# Buttons.net
KiCad netlist of a schematic drawn in Altium Designer
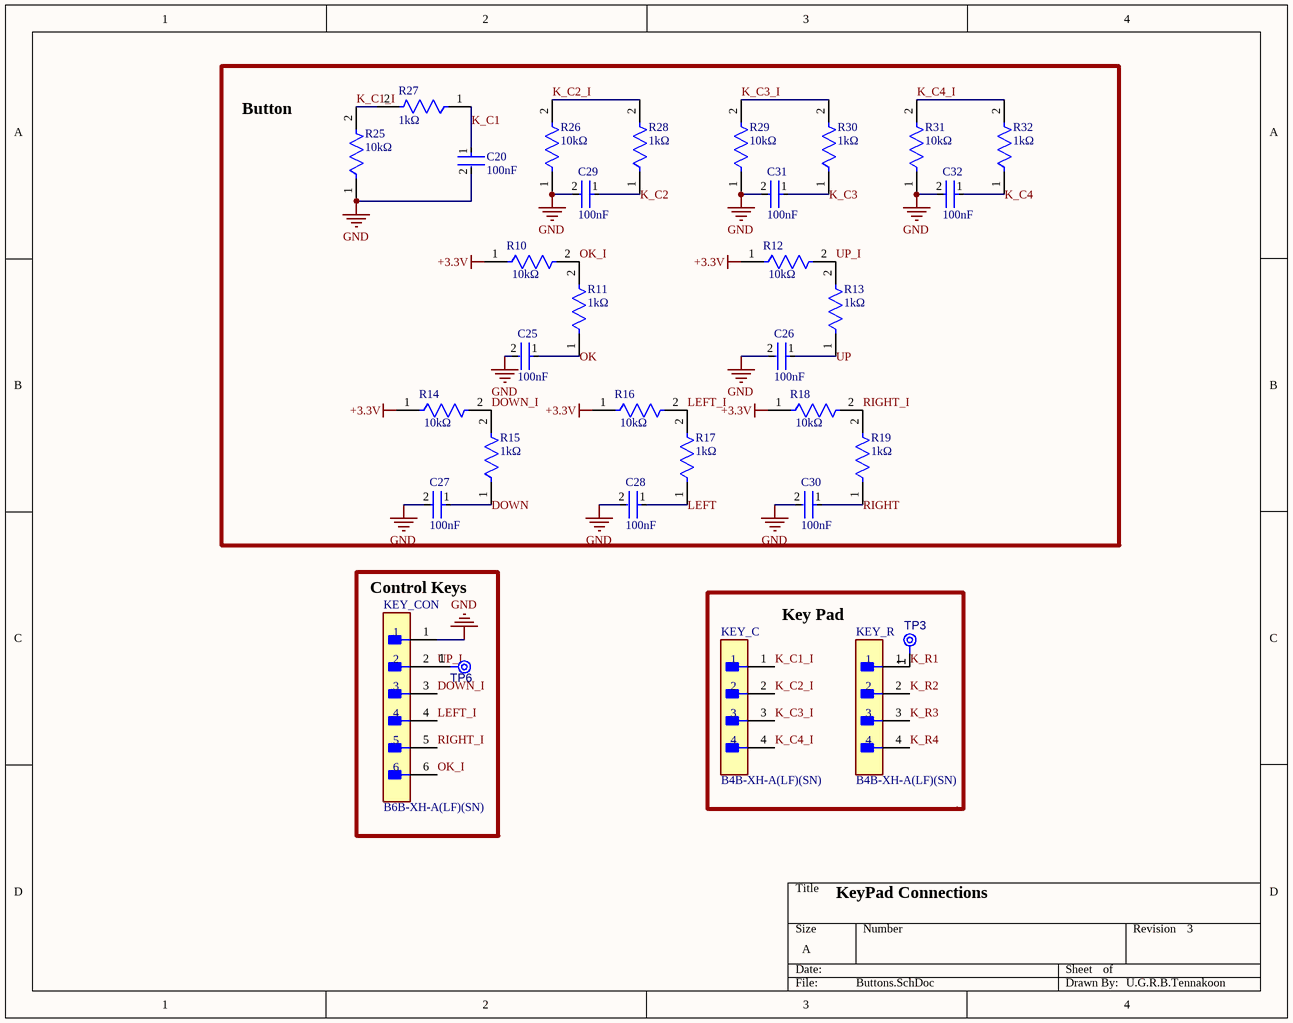
[diagram p0: Buttons.SchDoc]

(export (version "E")
  (design (tool "Eeschema 10.0.6"))
  (components
    (comp (ref "C20")
      (value "100nF")
      (footprint "FP-CL21-IPC_A")
      (description "CL21B104KCFWPNE CL21 Series 0805 100nF 100V ±10% Tolerance X7R Multilayer Ceramic Chip Capacitor")
      (fields (field (name "TOLERANCE") "10%"))
      (libsource (lib "Altium Content Vault") (part "b4654b650e69147ec39a6b967a45e02"))
    )
    (comp (ref "C25")
      (value "100nF")
      (footprint "FP-CL21-IPC_A")
      (description "CL21B104KCFWPNE CL21 Series 0805 100nF 100V ±10% Tolerance X7R Multilayer Ceramic Chip Capacitor")
      (fields (field (name "TOLERANCE") "10%"))
      (libsource (lib "Altium Content Vault") (part "b4654b650e69147ec39a6b967a45e02"))
    )
    (comp (ref "C26")
      (value "100nF")
      (footprint "FP-CL21-IPC_A")
      (description "CL21B104KCFWPNE CL21 Series 0805 100nF 100V ±10% Tolerance X7R Multilayer Ceramic Chip Capacitor")
      (fields (field (name "TOLERANCE") "10%"))
      (libsource (lib "Altium Content Vault") (part "b4654b650e69147ec39a6b967a45e02"))
    )
    (comp (ref "C27")
      (value "100nF")
      (footprint "FP-CL21-IPC_A")
      (description "CL21B104KCFWPNE CL21 Series 0805 100nF 100V ±10% Tolerance X7R Multilayer Ceramic Chip Capacitor")
      (fields (field (name "TOLERANCE") "10%"))
      (libsource (lib "Altium Content Vault") (part "b4654b650e69147ec39a6b967a45e02"))
    )
    (comp (ref "C28")
      (value "100nF")
      (footprint "FP-CL21-IPC_A")
      (description "CL21B104KCFWPNE CL21 Series 0805 100nF 100V ±10% Tolerance X7R Multilayer Ceramic Chip Capacitor")
      (fields (field (name "TOLERANCE") "10%"))
      (libsource (lib "Altium Content Vault") (part "b4654b650e69147ec39a6b967a45e02"))
    )
    (comp (ref "C29")
      (value "100nF")
      (footprint "FP-CL21-IPC_A")
      (description "CL21B104KCFWPNE CL21 Series 0805 100nF 100V ±10% Tolerance X7R Multilayer Ceramic Chip Capacitor")
      (fields (field (name "TOLERANCE") "10%"))
      (libsource (lib "Altium Content Vault") (part "b4654b650e69147ec39a6b967a45e02"))
    )
    (comp (ref "C30")
      (value "100nF")
      (footprint "FP-CL21-IPC_A")
      (description "CL21B104KCFWPNE CL21 Series 0805 100nF 100V ±10% Tolerance X7R Multilayer Ceramic Chip Capacitor")
      (fields (field (name "TOLERANCE") "10%"))
      (libsource (lib "Altium Content Vault") (part "b4654b650e69147ec39a6b967a45e02"))
    )
    (comp (ref "C31")
      (value "100nF")
      (footprint "FP-CL21-IPC_A")
      (description "CL21B104KCFWPNE CL21 Series 0805 100nF 100V ±10% Tolerance X7R Multilayer Ceramic Chip Capacitor")
      (fields (field (name "TOLERANCE") "10%"))
      (libsource (lib "Altium Content Vault") (part "b4654b650e69147ec39a6b967a45e02"))
    )
    (comp (ref "C32")
      (value "100nF")
      (footprint "FP-CL21-IPC_A")
      (description "CL21B104KCFWPNE CL21 Series 0805 100nF 100V ±10% Tolerance X7R Multilayer Ceramic Chip Capacitor")
      (fields (field (name "TOLERANCE") "10%"))
      (libsource (lib "Altium Content Vault") (part "b4654b650e69147ec39a6b967a45e02"))
    )
    (comp (ref "KEY_C")
      (value "B4B-XH-A(LF)(SN)")
      (footprint "FP-B4B-XH-A_LF_SN-MFG")
      (description "CONN HEADER VERT 4POS 2.5MM")
      (libsource (lib "Altium Content Vault") (part "299a8cea1bdcbc3624fe62c390fa72c"))
    )
    (comp (ref "KEY_CON")
      (value "B6B-XH-A(LF)(SN)")
      (footprint "FP-B6B-XH-A_LF_SN-MFG")
      (description "CONN HEADER VERT 6POS 2.5MM")
      (libsource (lib "Altium Content Vault") (part "f2cb566baf1c37ab5a3b8e90bbeafd6"))
    )
    (comp (ref "KEY_R")
      (value "B4B-XH-A(LF)(SN)")
      (footprint "FP-B4B-XH-A_LF_SN-MFG")
      (description "CONN HEADER VERT 4POS 2.5MM")
      (libsource (lib "Altium Content Vault") (part "299a8cea1bdcbc3624fe62c390fa72c"))
    )
    (comp (ref "R10")
      (value "10kΩ")
      (footprint "FP-SR0805-MFG")
      (description "RES SMD 0805 1/2W 1% 10K OHM")
      (fields (field (name "MANUFACTURER PART NUMBER") "SR0805FR-4710KL") (field (name "TOLERANCE") "0.01"))
      (libsource (lib "Altium Content Vault") (part "1029c3af85768c4190bb7ad29bc67b5"))
    )
    (comp (ref "R11")
      (value "1kΩ")
      (footprint "FP-SR0805-MFG")
      (description "RMC08051K5%N")
      (fields (field (name "MANUFACTURER PART NUMBER") "SR0805FR-4710KL") (field (name "TOLERANCE") "0.01"))
      (libsource (lib "Altium Content Vault") (part "1029c3af85768c4190bb7ad29bc67b5"))
    )
    (comp (ref "R12")
      (value "10kΩ")
      (footprint "FP-SR0805-MFG")
      (description "RES SMD 0805 1/2W 1% 10K OHM")
      (fields (field (name "MANUFACTURER PART NUMBER") "SR0805FR-4710KL") (field (name "TOLERANCE") "0.01"))
      (libsource (lib "Altium Content Vault") (part "1029c3af85768c4190bb7ad29bc67b5"))
    )
    (comp (ref "R13")
      (value "1kΩ")
      (footprint "FP-SR0805-MFG")
      (description "RMC08051K5%N")
      (fields (field (name "MANUFACTURER PART NUMBER") "SR0805FR-4710KL") (field (name "TOLERANCE") "0.01"))
      (libsource (lib "Altium Content Vault") (part "1029c3af85768c4190bb7ad29bc67b5"))
    )
    (comp (ref "R14")
      (value "10kΩ")
      (footprint "FP-SR0805-MFG")
      (description "RES SMD 0805 1/2W 1% 10K OHM")
      (fields (field (name "MANUFACTURER PART NUMBER") "SR0805FR-4710KL") (field (name "TOLERANCE") "0.01"))
      (libsource (lib "Altium Content Vault") (part "1029c3af85768c4190bb7ad29bc67b5"))
    )
    (comp (ref "R15")
      (value "1kΩ")
      (footprint "FP-SR0805-MFG")
      (description "RMC08051K5%N")
      (fields (field (name "MANUFACTURER PART NUMBER") "SR0805FR-4710KL") (field (name "TOLERANCE") "0.01"))
      (libsource (lib "Altium Content Vault") (part "1029c3af85768c4190bb7ad29bc67b5"))
    )
    (comp (ref "R16")
      (value "10kΩ")
      (footprint "FP-SR0805-MFG")
      (description "RES SMD 0805 1/2W 1% 10K OHM")
      (fields (field (name "MANUFACTURER PART NUMBER") "SR0805FR-4710KL") (field (name "TOLERANCE") "0.01"))
      (libsource (lib "Altium Content Vault") (part "1029c3af85768c4190bb7ad29bc67b5"))
    )
    (comp (ref "R17")
      (value "1kΩ")
      (footprint "FP-SR0805-MFG")
      (description "RMC08051K5%N")
      (fields (field (name "MANUFACTURER PART NUMBER") "SR0805FR-4710KL") (field (name "TOLERANCE") "0.01"))
      (libsource (lib "Altium Content Vault") (part "1029c3af85768c4190bb7ad29bc67b5"))
    )
    (comp (ref "R18")
      (value "10kΩ")
      (footprint "FP-SR0805-MFG")
      (description "RES SMD 0805 1/2W 1% 10K OHM")
      (fields (field (name "MANUFACTURER PART NUMBER") "SR0805FR-4710KL") (field (name "TOLERANCE") "0.01"))
      (libsource (lib "Altium Content Vault") (part "1029c3af85768c4190bb7ad29bc67b5"))
    )
    (comp (ref "R19")
      (value "1kΩ")
      (footprint "FP-SR0805-MFG")
      (description "RMC08051K5%N")
      (fields (field (name "MANUFACTURER PART NUMBER") "SR0805FR-4710KL") (field (name "TOLERANCE") "0.01"))
      (libsource (lib "Altium Content Vault") (part "1029c3af85768c4190bb7ad29bc67b5"))
    )
    (comp (ref "R25")
      (value "10kΩ")
      (footprint "FP-SR0805-MFG")
      (description "RES SMD 0805 1/2W 1% 10K OHM")
      (fields (field (name "MANUFACTURER PART NUMBER") "SR0805FR-4710KL") (field (name "TOLERANCE") "0.01"))
      (libsource (lib "Altium Content Vault") (part "1029c3af85768c4190bb7ad29bc67b5"))
    )
    (comp (ref "R26")
      (value "10kΩ")
      (footprint "FP-SR0805-MFG")
      (description "RES SMD 0805 1/2W 1% 10K OHM")
      (fields (field (name "MANUFACTURER PART NUMBER") "SR0805FR-4710KL") (field (name "TOLERANCE") "0.01"))
      (libsource (lib "Altium Content Vault") (part "1029c3af85768c4190bb7ad29bc67b5"))
    )
    (comp (ref "R27")
      (value "1kΩ")
      (footprint "FP-SR0805-MFG")
      (description "RMC08051K5%N")
      (fields (field (name "MANUFACTURER PART NUMBER") "SR0805FR-4710KL") (field (name "TOLERANCE") "0.01"))
      (libsource (lib "Altium Content Vault") (part "1029c3af85768c4190bb7ad29bc67b5"))
    )
    (comp (ref "R28")
      (value "1kΩ")
      (footprint "FP-SR0805-MFG")
      (description "RMC08051K5%N")
      (fields (field (name "MANUFACTURER PART NUMBER") "SR0805FR-4710KL") (field (name "TOLERANCE") "0.01"))
      (libsource (lib "Altium Content Vault") (part "1029c3af85768c4190bb7ad29bc67b5"))
    )
    (comp (ref "R29")
      (value "10kΩ")
      (footprint "FP-SR0805-MFG")
      (description "RES SMD 0805 1/2W 1% 10K OHM")
      (fields (field (name "MANUFACTURER PART NUMBER") "SR0805FR-4710KL") (field (name "TOLERANCE") "0.01"))
      (libsource (lib "Altium Content Vault") (part "1029c3af85768c4190bb7ad29bc67b5"))
    )
    (comp (ref "R30")
      (value "1kΩ")
      (footprint "FP-SR0805-MFG")
      (description "RMC08051K5%N")
      (fields (field (name "MANUFACTURER PART NUMBER") "SR0805FR-4710KL") (field (name "TOLERANCE") "0.01"))
      (libsource (lib "Altium Content Vault") (part "1029c3af85768c4190bb7ad29bc67b5"))
    )
    (comp (ref "R31")
      (value "10kΩ")
      (footprint "FP-SR0805-MFG")
      (description "RES SMD 0805 1/2W 1% 10K OHM")
      (fields (field (name "MANUFACTURER PART NUMBER") "SR0805FR-4710KL") (field (name "TOLERANCE") "0.01"))
      (libsource (lib "Altium Content Vault") (part "1029c3af85768c4190bb7ad29bc67b5"))
    )
    (comp (ref "R32")
      (value "1kΩ")
      (footprint "FP-SR0805-MFG")
      (description "RMC08051K5%N")
      (fields (field (name "MANUFACTURER PART NUMBER") "SR0805FR-4710KL") (field (name "TOLERANCE") "0.01"))
      (libsource (lib "Altium Content Vault") (part "1029c3af85768c4190bb7ad29bc67b5"))
    )
    (comp (ref "TP3")
      (value "TPAD6R")
      (footprint "TP06R")
      (description "0.6mm round")
      (libsource (lib "ravindu tennakoon") (part "CMP-001-0001-4"))
    )
    (comp (ref "TP6")
      (value "TPAD6R")
      (footprint "TP06R")
      (description "0.6mm round")
      (libsource (lib "ravindu tennakoon") (part "CMP-001-0001-4"))
    )
  )
  (nets
    (net (code "1") (name "+3.3V") (class "Default")
      (node (ref "R10") (pin "1") (pinfunction "1_1") (pintype "passive"))
      (node (ref "R12") (pin "1") (pinfunction "1_1") (pintype "passive"))
      (node (ref "R14") (pin "1") (pinfunction "1_1") (pintype "passive"))
      (node (ref "R16") (pin "1") (pinfunction "1_1") (pintype "passive"))
      (node (ref "R18") (pin "1") (pinfunction "1_1") (pintype "passive"))
    )
    (net (code "2") (name "/DOWN") (class "Default")
      (node (ref "C27") (pin "1") (pinfunction "1_1") (pintype "passive"))
      (node (ref "R15") (pin "1") (pinfunction "1_1") (pintype "passive"))
    )
    (net (code "3") (name "/DOWN_I") (class "Default")
      (node (ref "KEY_CON") (pin "3") (pinfunction "3_3") (pintype "passive"))
      (node (ref "R14") (pin "2") (pinfunction "2_2") (pintype "passive"))
      (node (ref "R15") (pin "2") (pinfunction "2_2") (pintype "passive"))
    )
    (net (code "4") (name "/K_C1") (class "Default")
      (node (ref "C20") (pin "1") (pinfunction "1_1") (pintype "passive"))
      (node (ref "R27") (pin "1") (pinfunction "1_1") (pintype "passive"))
    )
    (net (code "5") (name "/K_C1_I") (class "Default")
      (node (ref "KEY_C") (pin "1") (pinfunction "1_1") (pintype "passive"))
      (node (ref "R25") (pin "2") (pinfunction "2_2") (pintype "passive"))
      (node (ref "R27") (pin "2") (pinfunction "2_2") (pintype "passive"))
    )
    (net (code "6") (name "/K_C2") (class "Default")
      (node (ref "C29") (pin "1") (pinfunction "1_1") (pintype "passive"))
      (node (ref "R28") (pin "1") (pinfunction "1_1") (pintype "passive"))
    )
    (net (code "7") (name "/K_C2_I") (class "Default")
      (node (ref "KEY_C") (pin "2") (pinfunction "2_2") (pintype "passive"))
      (node (ref "R26") (pin "2") (pinfunction "2_2") (pintype "passive"))
      (node (ref "R28") (pin "2") (pinfunction "2_2") (pintype "passive"))
    )
    (net (code "8") (name "/K_C3") (class "Default")
      (node (ref "C31") (pin "1") (pinfunction "1_1") (pintype "passive"))
      (node (ref "R30") (pin "1") (pinfunction "1_1") (pintype "passive"))
    )
    (net (code "9") (name "/K_C3_I") (class "Default")
      (node (ref "KEY_C") (pin "3") (pinfunction "3_3") (pintype "passive"))
      (node (ref "R29") (pin "2") (pinfunction "2_2") (pintype "passive"))
      (node (ref "R30") (pin "2") (pinfunction "2_2") (pintype "passive"))
    )
    (net (code "10") (name "/K_C4") (class "Default")
      (node (ref "C32") (pin "1") (pinfunction "1_1") (pintype "passive"))
      (node (ref "R32") (pin "1") (pinfunction "1_1") (pintype "passive"))
    )
    (net (code "11") (name "/K_C4_I") (class "Default")
      (node (ref "KEY_C") (pin "4") (pinfunction "4_4") (pintype "passive"))
      (node (ref "R31") (pin "2") (pinfunction "2_2") (pintype "passive"))
      (node (ref "R32") (pin "2") (pinfunction "2_2") (pintype "passive"))
    )
    (net (code "12") (name "/K_R1") (class "Default")
      (node (ref "KEY_R") (pin "1") (pinfunction "1_1") (pintype "passive"))
      (node (ref "TP3") (pin "1") (pinfunction "TP_1") (pintype "passive"))
    )
    (net (code "13") (name "/K_R2") (class "Default")
      (node (ref "KEY_R") (pin "2") (pinfunction "2_2") (pintype "passive"))
    )
    (net (code "14") (name "/K_R3") (class "Default")
      (node (ref "KEY_R") (pin "3") (pinfunction "3_3") (pintype "passive"))
    )
    (net (code "15") (name "/K_R4") (class "Default")
      (node (ref "KEY_R") (pin "4") (pinfunction "4_4") (pintype "passive"))
    )
    (net (code "16") (name "/LEFT") (class "Default")
      (node (ref "C28") (pin "1") (pinfunction "1_1") (pintype "passive"))
      (node (ref "R17") (pin "1") (pinfunction "1_1") (pintype "passive"))
    )
    (net (code "17") (name "/LEFT_I") (class "Default")
      (node (ref "KEY_CON") (pin "4") (pinfunction "4_4") (pintype "passive"))
      (node (ref "R16") (pin "2") (pinfunction "2_2") (pintype "passive"))
      (node (ref "R17") (pin "2") (pinfunction "2_2") (pintype "passive"))
    )
    (net (code "18") (name "/OK") (class "Default")
      (node (ref "C25") (pin "1") (pinfunction "1_1") (pintype "passive"))
      (node (ref "R11") (pin "1") (pinfunction "1_1") (pintype "passive"))
    )
    (net (code "19") (name "/OK_I") (class "Default")
      (node (ref "KEY_CON") (pin "6") (pinfunction "6_6") (pintype "passive"))
      (node (ref "R10") (pin "2") (pinfunction "2_2") (pintype "passive"))
      (node (ref "R11") (pin "2") (pinfunction "2_2") (pintype "passive"))
    )
    (net (code "20") (name "/RIGHT") (class "Default")
      (node (ref "C30") (pin "1") (pinfunction "1_1") (pintype "passive"))
      (node (ref "R19") (pin "1") (pinfunction "1_1") (pintype "passive"))
    )
    (net (code "21") (name "/RIGHT_I") (class "Default")
      (node (ref "KEY_CON") (pin "5") (pinfunction "5_5") (pintype "passive"))
      (node (ref "R18") (pin "2") (pinfunction "2_2") (pintype "passive"))
      (node (ref "R19") (pin "2") (pinfunction "2_2") (pintype "passive"))
    )
    (net (code "22") (name "/UP") (class "Default")
      (node (ref "C26") (pin "1") (pinfunction "1_1") (pintype "passive"))
      (node (ref "R13") (pin "1") (pinfunction "1_1") (pintype "passive"))
    )
    (net (code "23") (name "/UP_I") (class "Default")
      (node (ref "KEY_CON") (pin "2") (pinfunction "2_2") (pintype "passive"))
      (node (ref "R12") (pin "2") (pinfunction "2_2") (pintype "passive"))
      (node (ref "R13") (pin "2") (pinfunction "2_2") (pintype "passive"))
      (node (ref "TP6") (pin "1") (pinfunction "TP_1") (pintype "passive"))
    )
    (net (code "24") (name "GND") (class "Default")
      (node (ref "C20") (pin "2") (pinfunction "2_2") (pintype "passive"))
      (node (ref "C25") (pin "2") (pinfunction "2_2") (pintype "passive"))
      (node (ref "C26") (pin "2") (pinfunction "2_2") (pintype "passive"))
      (node (ref "C27") (pin "2") (pinfunction "2_2") (pintype "passive"))
      (node (ref "C28") (pin "2") (pinfunction "2_2") (pintype "passive"))
      (node (ref "C29") (pin "2") (pinfunction "2_2") (pintype "passive"))
      (node (ref "C30") (pin "2") (pinfunction "2_2") (pintype "passive"))
      (node (ref "C31") (pin "2") (pinfunction "2_2") (pintype "passive"))
      (node (ref "C32") (pin "2") (pinfunction "2_2") (pintype "passive"))
      (node (ref "KEY_CON") (pin "1") (pinfunction "1_1") (pintype "passive"))
      (node (ref "R25") (pin "1") (pinfunction "1_1") (pintype "passive"))
      (node (ref "R26") (pin "1") (pinfunction "1_1") (pintype "passive"))
      (node (ref "R29") (pin "1") (pinfunction "1_1") (pintype "passive"))
      (node (ref "R31") (pin "1") (pinfunction "1_1") (pintype "passive"))
    )
  )
)
